# Shield.net
KiCad netlist of a schematic drawn in Altium Designer
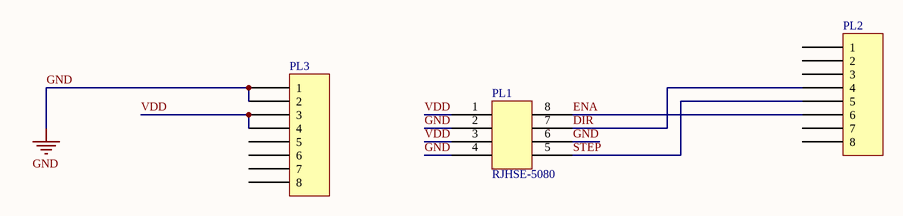
[diagram p0: Shield.SchDoc]

(export (version "E")
  (design (tool "Eeschema 10.0.6"))
  (components
    (comp (ref "PL1")
      (value "RJHSE-5080")
      (footprint "AMPHENOL RJHSE-5080")
      (description "CONN MOD JACK 8P8C R/A UNSHLD")
      (libsource (lib "ON Development Vault") (part "2x4"))
    )
    (comp (ref "PL2")
      (value "8-pin Male Header 2.54mm")
      (footprint "8-pin 2.54mm header")
      (libsource (lib "ON Development Vault") (part "8Pin Header"))
    )
    (comp (ref "PL3")
      (value "8-pin Male Header 2.54mm")
      (footprint "8-pin 2.54mm header")
      (libsource (lib "ON Development Vault") (part "8Pin Header"))
    )
  )
  (nets
    (net (code "1") (name "/DIR") (class "Default")
      (node (ref "PL1") (pin "7") (pinfunction "7_7") (pintype "passive"))
      (node (ref "PL2") (pin "4") (pinfunction "4_4") (pintype "passive"))
    )
    (net (code "2") (name "/ENA") (class "Default")
      (node (ref "PL1") (pin "8") (pinfunction "8_8") (pintype "passive"))
      (node (ref "PL2") (pin "6") (pinfunction "6_6") (pintype "passive"))
    )
    (net (code "3") (name "/STEP") (class "Default")
      (node (ref "PL1") (pin "5") (pinfunction "5_5") (pintype "passive"))
      (node (ref "PL2") (pin "5") (pinfunction "5_5") (pintype "passive"))
    )
    (net (code "4") (name "/VDD") (class "Default")
      (node (ref "PL1") (pin "1") (pinfunction "1_1") (pintype "passive"))
      (node (ref "PL1") (pin "3") (pinfunction "3_3") (pintype "passive"))
      (node (ref "PL3") (pin "3") (pinfunction "3_3") (pintype "passive"))
      (node (ref "PL3") (pin "4") (pinfunction "4_4") (pintype "passive"))
    )
    (net (code "5") (name "GND") (class "Default")
      (node (ref "PL1") (pin "2") (pinfunction "2_2") (pintype "passive"))
      (node (ref "PL1") (pin "4") (pinfunction "4_4") (pintype "passive"))
      (node (ref "PL1") (pin "6") (pinfunction "6_6") (pintype "passive"))
      (node (ref "PL3") (pin "1") (pinfunction "1_1") (pintype "passive"))
      (node (ref "PL3") (pin "2") (pinfunction "2_2") (pintype "passive"))
    )
    (net (code "6") (name "unconnected-(PL2-Pad1)") (class "Default")
      (node (ref "PL2") (pin "1") (pinfunction "1_1") (pintype "passive"))
    )
    (net (code "7") (name "unconnected-(PL2-Pad2)") (class "Default")
      (node (ref "PL2") (pin "2") (pinfunction "2_2") (pintype "passive"))
    )
    (net (code "8") (name "unconnected-(PL2-Pad3)") (class "Default")
      (node (ref "PL2") (pin "3") (pinfunction "3_3") (pintype "passive"))
    )
    (net (code "9") (name "unconnected-(PL2-Pad7)") (class "Default")
      (node (ref "PL2") (pin "7") (pinfunction "7_7") (pintype "passive"))
    )
    (net (code "10") (name "unconnected-(PL2-Pad8)") (class "Default")
      (node (ref "PL2") (pin "8") (pinfunction "8_8") (pintype "passive"))
    )
    (net (code "11") (name "unconnected-(PL3-Pad5)") (class "Default")
      (node (ref "PL3") (pin "5") (pinfunction "5_5") (pintype "passive"))
    )
    (net (code "12") (name "unconnected-(PL3-Pad6)") (class "Default")
      (node (ref "PL3") (pin "6") (pinfunction "6_6") (pintype "passive"))
    )
    (net (code "13") (name "unconnected-(PL3-Pad7)") (class "Default")
      (node (ref "PL3") (pin "7") (pinfunction "7_7") (pintype "passive"))
    )
    (net (code "14") (name "unconnected-(PL3-Pad8)") (class "Default")
      (node (ref "PL3") (pin "8") (pinfunction "8_8") (pintype "passive"))
    )
  )
)
